# vRef_Therm_Mod.net
KiCad netlist of a schematic drawn in EAGLE
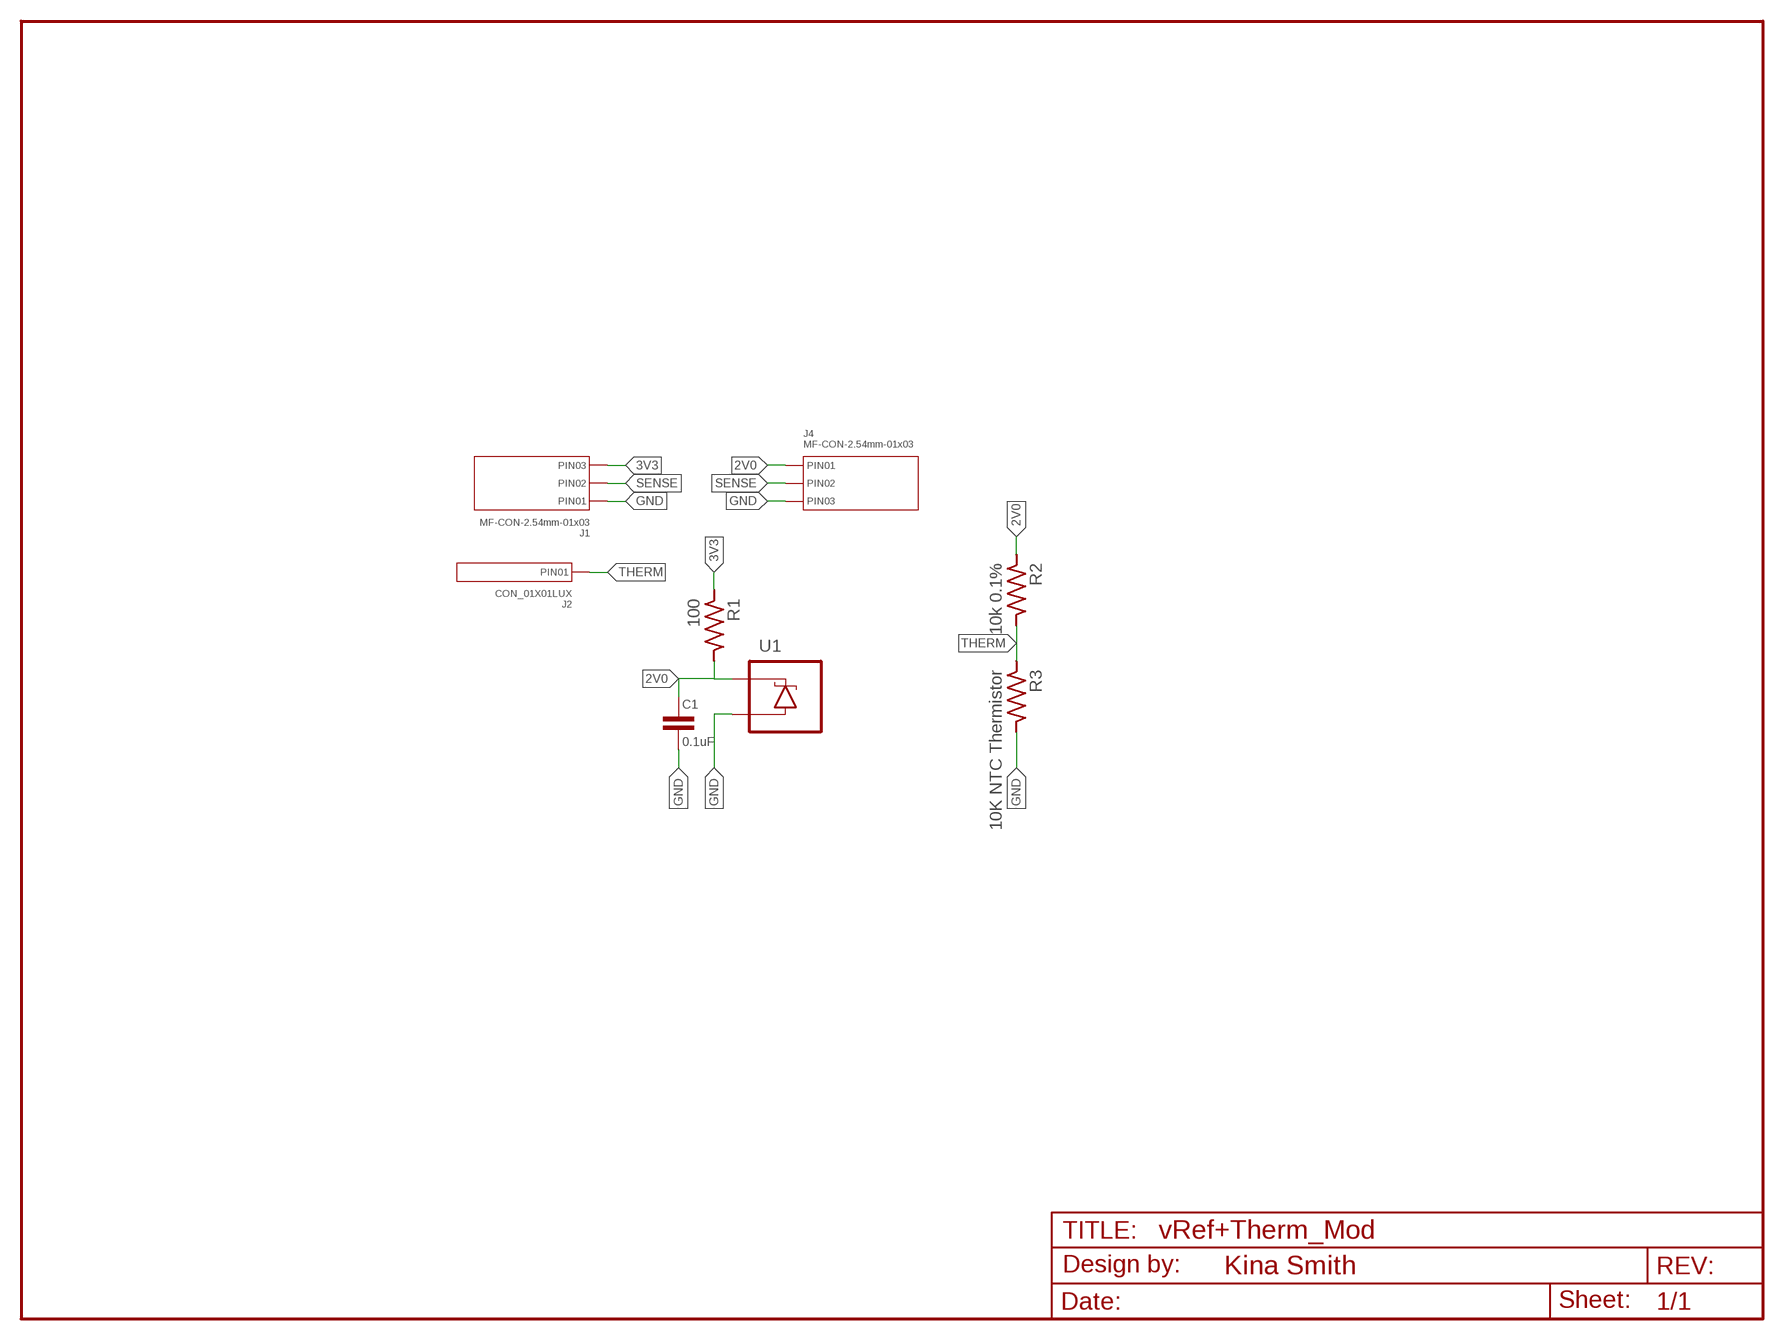
[diagram p0: schematic, sheet 1]

(export (version "E")
  (design (tool "Eeschema 10.0.6"))
  (components
    (comp (ref "C1")
      (value "0.1uF")
      (footprint "eagle-import:C0603-N")
      (libsource (lib "eagle-import") (part "CAPACITOR_NP0603-N"))
    )
    (comp (ref "FRAME1")
      (value "FRAME-LETTERNO_PACKAGE")
      (footprint "eagle-import:DUMMY")
      (fields (field (name "PARTNO") "NA") (field (name "DESIGNER") "Nobody"))
      (libsource (lib "eagle-import") (part "FRAME-LETTERNO_PACKAGE"))
    )
    (comp (ref "J1")
      (value "MF-CON-2.54mm-01x03")
      (footprint "eagle-import:PTH_2.54MM_01X03")
      (fields (field (name "HOUSEPART") "YES"))
      (libsource (lib "eagle-import") (part "CON_01X03_PTH_2.54MM"))
    )
    (comp (ref "J2")
      (value "CON_01X01LUX")
      (footprint "eagle-import:1X01_LUXEON-PAD")
      (libsource (lib "eagle-import") (part "CON_01X01LUX"))
    )
    (comp (ref "J4")
      (value "MF-CON-2.54mm-01x03")
      (footprint "eagle-import:PTH_2.54MM_01X03")
      (fields (field (name "HOUSEPART") "YES"))
      (libsource (lib "eagle-import") (part "CON_01X03_PTH_2.54MM"))
    )
    (comp (ref "R1")
      (value "100")
      (footprint "eagle-import:R0603-N")
      (libsource (lib "eagle-import") (part "RESISTOR0603-N"))
    )
    (comp (ref "R2")
      (value "10k 0.1%")
      (footprint "eagle-import:R0603-N")
      (libsource (lib "eagle-import") (part "RESISTOR0603-N"))
    )
    (comp (ref "R3")
      (value "10K NTC Thermistor")
      (footprint "eagle-import:R0603-N")
      (libsource (lib "eagle-import") (part "RESISTOR0603-N"))
    )
    (comp (ref "U1")
      (value "LM4040-SOT-23-3")
      (footprint "eagle-import:SOT23-3")
      (fields (field (name "PARTNO") "LM4040AIM3-2.0/NOPB "))
      (libsource (lib "eagle-import") (part "LM4040-SOT-23-3"))
    )
  )
  (nets
    (net (code "1") (name "2V0") (class "Default")
      (node (ref "C1") (pin "1") (pinfunction "1_1") (pintype "passive"))
      (node (ref "J4") (pin "P$1") (pinfunction "PIN1_P$1") (pintype "bidirectional"))
      (node (ref "R1") (pin "2") (pinfunction "P$2_2") (pintype "passive"))
      (node (ref "R2") (pin "1") (pinfunction "P$1_1") (pintype "passive"))
      (node (ref "U1") (pin "1") (pinfunction "C_1") (pintype "bidirectional"))
    )
    (net (code "2") (name "3V3") (class "Default")
      (node (ref "J1") (pin "P$3") (pinfunction "PIN3_P$3") (pintype "bidirectional"))
      (node (ref "R1") (pin "1") (pinfunction "P$1_1") (pintype "passive"))
    )
    (net (code "3") (name "GND") (class "Default")
      (node (ref "C1") (pin "2") (pinfunction "2_2") (pintype "passive"))
      (node (ref "J1") (pin "P$1") (pinfunction "PIN1_P$1") (pintype "bidirectional"))
      (node (ref "J4") (pin "P$3") (pinfunction "PIN3_P$3") (pintype "bidirectional"))
      (node (ref "R3") (pin "2") (pinfunction "P$2_2") (pintype "passive"))
      (node (ref "U1") (pin "2") (pinfunction "A_2") (pintype "bidirectional"))
    )
    (net (code "4") (name "SENSE") (class "Default")
      (node (ref "J1") (pin "P$2") (pinfunction "PIN2_P$2") (pintype "bidirectional"))
      (node (ref "J4") (pin "P$2") (pinfunction "PIN2_P$2") (pintype "bidirectional"))
    )
    (net (code "5") (name "THERM") (class "Default")
      (node (ref "J2") (pin "P$1") (pinfunction "PIN1_P$1") (pintype "bidirectional"))
      (node (ref "R2") (pin "2") (pinfunction "P$2_2") (pintype "passive"))
      (node (ref "R3") (pin "1") (pinfunction "P$1_1") (pintype "passive"))
    )
  )
)
